# power2.net
KiCad netlist of a schematic drawn in Altium Designer
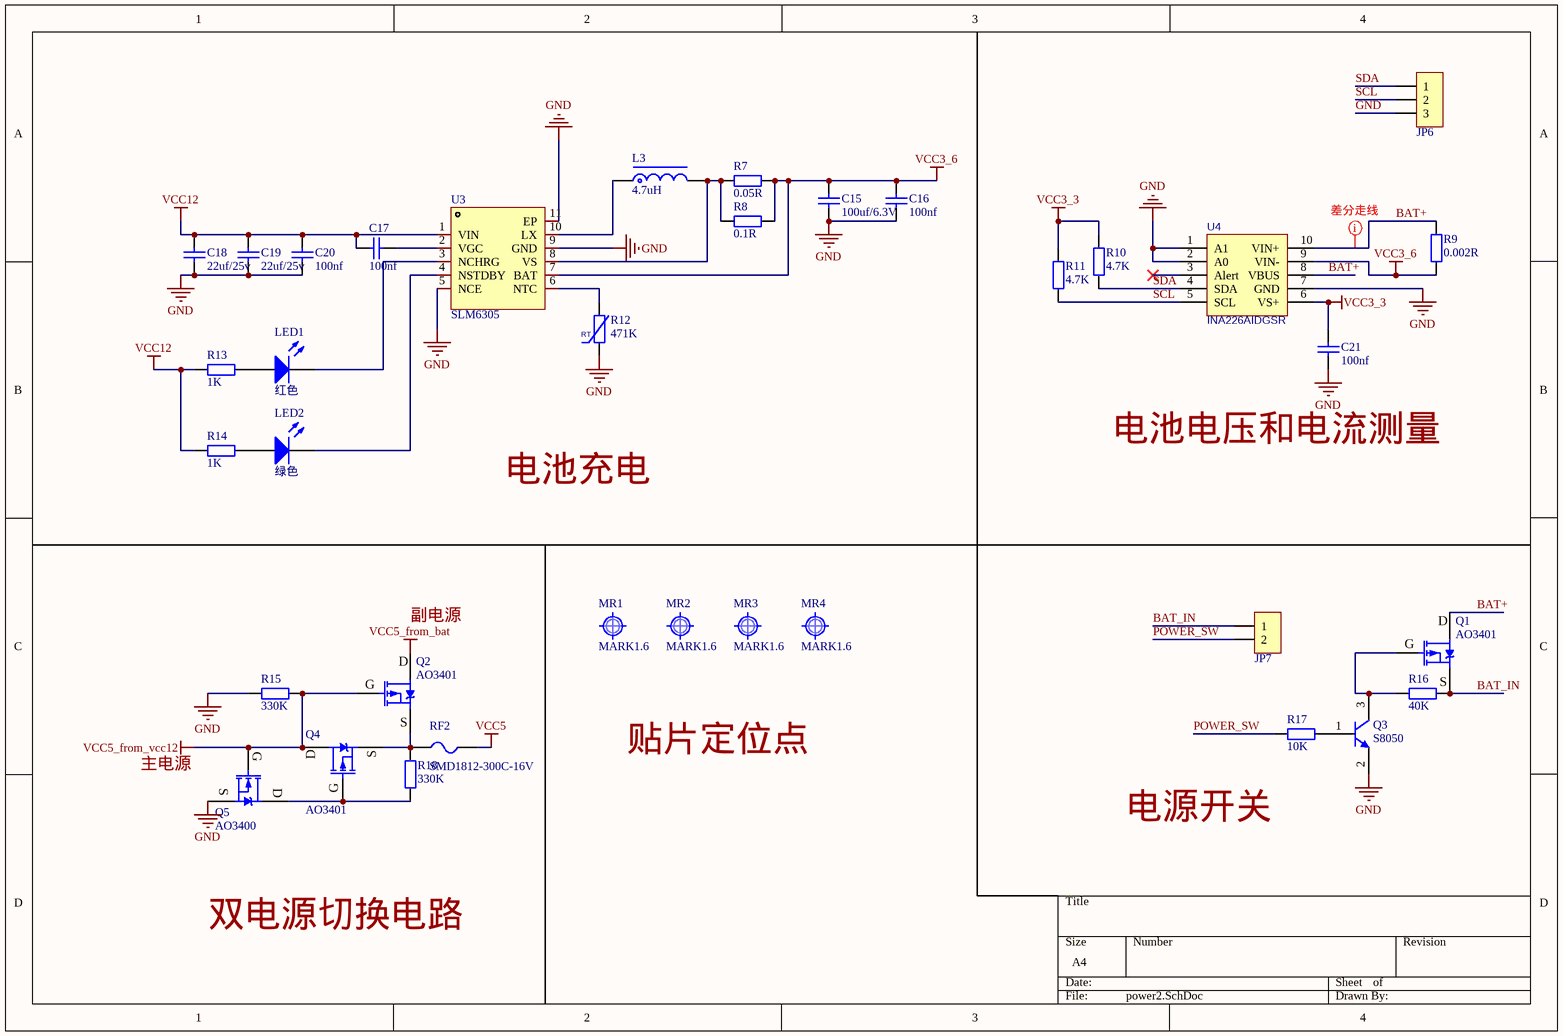
[diagram p0: power2.SchDoc]

(export (version "E")
  (design (tool "Eeschema 10.0.6"))
  (components
    (comp (ref "C15")
      (value "100uf/6.3V")
      (footprint "C1206_L")
      (description "贴片电容/MLCC电容")
      (libsource (lib "0.1 - 电阻-电容-电感-保险丝-晶振-晶体-磁珠-电位器-法拉电容-馈通电容") (part "C"))
    )
    (comp (ref "C16")
      (value "100nf")
      (footprint "C0603_L")
      (description "贴片电容/MLCC电容")
      (libsource (lib "0.1 - 电阻-电容-电感-保险丝-晶振-晶体-磁珠-电位器-法拉电容-馈通电容") (part "C"))
    )
    (comp (ref "C17")
      (value "100nf")
      (footprint "C0603_L")
      (description "贴片电容/MLCC电容")
      (libsource (lib "0.1 - 电阻-电容-电感-保险丝-晶振-晶体-磁珠-电位器-法拉电容-馈通电容") (part "C"))
    )
    (comp (ref "C18")
      (value "22uf/25v")
      (footprint "C0805_L")
      (description "贴片电容/MLCC电容")
      (libsource (lib "0.1 - 电阻-电容-电感-保险丝-晶振-晶体-磁珠-电位器-法拉电容-馈通电容") (part "C"))
    )
    (comp (ref "C19")
      (value "22uf/25v")
      (footprint "C0805_L")
      (description "贴片电容/MLCC电容")
      (libsource (lib "0.1 - 电阻-电容-电感-保险丝-晶振-晶体-磁珠-电位器-法拉电容-馈通电容") (part "C"))
    )
    (comp (ref "C20")
      (value "100nf")
      (footprint "C0603_L")
      (description "贴片电容/MLCC电容")
      (libsource (lib "0.1 - 电阻-电容-电感-保险丝-晶振-晶体-磁珠-电位器-法拉电容-馈通电容") (part "C"))
    )
    (comp (ref "C21")
      (value "100nf")
      (footprint "C0603_L")
      (description "贴片电容/MLCC电容")
      (libsource (lib "0.1 - 电阻-电容-电感-保险丝-晶振-晶体-磁珠-电位器-法拉电容-馈通电容") (part "C"))
    )
    (comp (ref "JP6")
      (value "HDR-1X3")
      (footprint "HDR2.54-LI-3P")
      (description "3P接插件")
      (libsource (lib "5.5 - 2.54mm连接器(KF2EDGK_XH2.54_2.54排针排母)") (part "Header 3"))
    )
    (comp (ref "JP7")
      (value "HDR-1X2")
      (footprint "PH2.0-W-2P")
      (description "2P接插件")
      (libsource (lib "5.4 - 2.0mm连接器(PHB2.0_PHD2.0_2.0排针排母)") (part "Header 2"))
    )
    (comp (ref "L3")
      (value "4.7uH")
      (footprint "CD53")
      (description "CD系列贴片线绕功率电感")
      (libsource (lib "0.1 - 电阻-电容-电感-保险丝-晶振-晶体-磁珠-电位器-法拉电容-馈通电容") (part "L-SMD"))
    )
    (comp (ref "LED1")
      (value "红色")
      (footprint "LED0603_Y")
      (description "贴片LED")
      (libsource (lib "0.3 - LED发光二极管-IR二极管_接收管-光耦") (part "LED"))
    )
    (comp (ref "LED2")
      (value "绿色")
      (footprint "LED0603_Y")
      (description "贴片LED")
      (libsource (lib "0.3 - LED发光二极管-IR二极管_接收管-光耦") (part "LED"))
    )
    (comp (ref "MR1")
      (value "MARK1.6")
      (footprint "Mark 1")
      (description "光学定位点")
      (libsource (lib "0.5 - 按键_开关_蜂鸣器_电池_测试点_Mark点_铜柱") (part "MARK"))
    )
    (comp (ref "MR2")
      (value "MARK1.6")
      (footprint "Mark 1")
      (description "光学定位点")
      (libsource (lib "0.5 - 按键_开关_蜂鸣器_电池_测试点_Mark点_铜柱") (part "MARK"))
    )
    (comp (ref "MR3")
      (value "MARK1.6")
      (footprint "Mark 1")
      (description "光学定位点")
      (libsource (lib "0.5 - 按键_开关_蜂鸣器_电池_测试点_Mark点_铜柱") (part "MARK"))
    )
    (comp (ref "MR4")
      (value "MARK1.6")
      (footprint "Mark 1")
      (description "光学定位点")
      (libsource (lib "0.5 - 按键_开关_蜂鸣器_电池_测试点_Mark点_铜柱") (part "MARK"))
    )
    (comp (ref "Q1")
      (value "AO3401")
      (footprint "SOT23-3N")
      (description "P沟道 30V/4.2A")
      (libsource (lib "0.4 - 三极管-场效应管-可控硅") (part "AO3401"))
    )
    (comp (ref "Q2")
      (value "AO3401")
      (footprint "SOT23-3N")
      (description "P沟道 30V/4.2A")
      (libsource (lib "0.4 - 三极管-场效应管-可控硅") (part "AO3401"))
    )
    (comp (ref "Q3")
      (value "S8050")
      (footprint "SOT23-3M")
      (description "NPN三极管")
      (libsource (lib "0.4 - 三极管-场效应管-可控硅") (part "BCP68"))
    )
    (comp (ref "Q4")
      (value "AO3401")
      (footprint "SOT23-3N")
      (description "P沟道 30V/4.2A")
      (libsource (lib "0.4 - 三极管-场效应管-可控硅") (part "AO3401"))
    )
    (comp (ref "Q5")
      (value "AO3400")
      (footprint "SOT23-3N")
      (description "N沟道 30V/4.2A")
      (libsource (lib "0.4 - 三极管-场效应管-可控硅") (part "AO3400"))
    )
    (comp (ref "R7")
      (value "0.05R")
      (footprint "R1206_L")
      (description "贴片电阻")
      (libsource (lib "0.1 - 电阻-电容-电感-保险丝-晶振-晶体-磁珠-电位器-法拉电容-馈通电容") (part "R"))
    )
    (comp (ref "R8")
      (value "0.1R")
      (footprint "R1206_L")
      (description "贴片电阻")
      (libsource (lib "0.1 - 电阻-电容-电感-保险丝-晶振-晶体-磁珠-电位器-法拉电容-馈通电容") (part "R"))
    )
    (comp (ref "R9")
      (value "0.002R")
      (footprint "R2512_M")
      (description "贴片电阻")
      (libsource (lib "0.1 - 电阻-电容-电感-保险丝-晶振-晶体-磁珠-电位器-法拉电容-馈通电容") (part "R"))
    )
    (comp (ref "R10")
      (value "4.7K")
      (footprint "R0603_L")
      (description "贴片电阻")
      (libsource (lib "0.1 - 电阻-电容-电感-保险丝-晶振-晶体-磁珠-电位器-法拉电容-馈通电容") (part "R"))
    )
    (comp (ref "R11")
      (value "4.7K")
      (footprint "R0603_L")
      (description "贴片电阻")
      (libsource (lib "0.1 - 电阻-电容-电感-保险丝-晶振-晶体-磁珠-电位器-法拉电容-馈通电容") (part "R"))
    )
    (comp (ref "R12")
      (value "471K")
      (footprint "PK0406")
      (description "热敏电阻")
      (libsource (lib "0.1 - 电阻-电容-电感-保险丝-晶振-晶体-磁珠-电位器-法拉电容-馈通电容") (part "RT"))
    )
    (comp (ref "R13")
      (value "1K")
      (footprint "R0603_L")
      (description "贴片电阻")
      (libsource (lib "0.1 - 电阻-电容-电感-保险丝-晶振-晶体-磁珠-电位器-法拉电容-馈通电容") (part "R"))
    )
    (comp (ref "R14")
      (value "1K")
      (footprint "R0603_L")
      (description "贴片电阻")
      (libsource (lib "0.1 - 电阻-电容-电感-保险丝-晶振-晶体-磁珠-电位器-法拉电容-馈通电容") (part "R"))
    )
    (comp (ref "R15")
      (value "330K")
      (footprint "R0603_L")
      (description "贴片电阻")
      (libsource (lib "0.1 - 电阻-电容-电感-保险丝-晶振-晶体-磁珠-电位器-法拉电容-馈通电容") (part "R"))
    )
    (comp (ref "R16")
      (value "40K")
      (footprint "R0603_L")
      (description "贴片电阻")
      (libsource (lib "0.1 - 电阻-电容-电感-保险丝-晶振-晶体-磁珠-电位器-法拉电容-馈通电容") (part "R"))
    )
    (comp (ref "R17")
      (value "10K")
      (footprint "R0603_L")
      (description "贴片电阻")
      (libsource (lib "0.1 - 电阻-电容-电感-保险丝-晶振-晶体-磁珠-电位器-法拉电容-馈通电容") (part "R"))
    )
    (comp (ref "R18")
      (value "330K")
      (footprint "R0603_L")
      (description "贴片电阻")
      (libsource (lib "0.1 - 电阻-电容-电感-保险丝-晶振-晶体-磁珠-电位器-法拉电容-馈通电容") (part "R"))
    )
    (comp (ref "RF2")
      (value "SMD1812-300C-16V")
      (footprint "F1812")
      (description "PPTC自恢复保险丝")
      (libsource (lib "0.1 - 电阻-电容-电感-保险丝-晶振-晶体-磁珠-电位器-法拉电容-馈通电容") (part "FUSE-PPTC"))
    )
    (comp (ref "U3")
      (value "SLM6305")
      (footprint "DFN10-L3.0-W3.0-P0.5_EP")
      (description "1锂电池充电ic 2.5a 4.2v 4V~26V输入")
      (fields (field (name "MANUFACTURER") "无锡松朗微"))
      (libsource (lib "HT") (part "SLM6305"))
    )
    (comp (ref "U4")
      (value "INA226AIDGSR")
      (footprint "MSOP10_N")
      (description "双向电流/功率监视器芯片")
      (libsource (lib "0.8 - 常见芯片") (part "INA226"))
    )
  )
  (nets
    (net (code "1") (name "/BAT+") (class "Default")
      (node (ref "Q1") (pin "3") (pinfunction "D_3") (pintype "passive"))
      (node (ref "R9") (pin "1") (pinfunction "1_1") (pintype "passive"))
      (node (ref "U4") (pin "10") (pinfunction "VIN+_10") (pintype "passive"))
      (node (ref "U4") (pin "8") (pinfunction "VBUS_8") (pintype "passive"))
    )
    (net (code "2") (name "/BAT_IN") (class "Default")
      (node (ref "JP7") (pin "1") (pinfunction "1_1") (pintype "passive"))
      (node (ref "Q1") (pin "2") (pinfunction "S_2") (pintype "passive"))
      (node (ref "R16") (pin "2") (pinfunction "2_2") (pintype "passive"))
    )
    (net (code "3") (name "/POWER_SW") (class "Default")
      (node (ref "JP7") (pin "2") (pinfunction "2_2") (pintype "passive"))
      (node (ref "R17") (pin "1") (pinfunction "1_1") (pintype "passive"))
    )
    (net (code "4") (name "/SCL") (class "Default")
      (node (ref "JP6") (pin "2") (pinfunction "2_2") (pintype "passive"))
      (node (ref "R11") (pin "1") (pinfunction "1_1") (pintype "passive"))
      (node (ref "U4") (pin "5") (pinfunction "SCL_5") (pintype "passive"))
    )
    (net (code "5") (name "/SDA") (class "Default")
      (node (ref "JP6") (pin "1") (pinfunction "1_1") (pintype "passive"))
      (node (ref "R10") (pin "1") (pinfunction "1_1") (pintype "passive"))
      (node (ref "U4") (pin "4") (pinfunction "SDA_4") (pintype "passive"))
    )
    (net (code "6") (name "GND") (class "Default")
      (node (ref "C15") (pin "1") (pinfunction "1_1") (pintype "passive"))
      (node (ref "C16") (pin "1") (pinfunction "1_1") (pintype "passive"))
      (node (ref "C18") (pin "1") (pinfunction "1_1") (pintype "passive"))
      (node (ref "C19") (pin "1") (pinfunction "1_1") (pintype "passive"))
      (node (ref "C20") (pin "2") (pinfunction "2_2") (pintype "passive"))
      (node (ref "C21") (pin "1") (pinfunction "1_1") (pintype "passive"))
      (node (ref "JP6") (pin "3") (pinfunction "3_3") (pintype "passive"))
      (node (ref "Q3") (pin "2") (pinfunction "E_2") (pintype "passive"))
      (node (ref "Q5") (pin "2") (pinfunction "S_2") (pintype "passive"))
      (node (ref "R12") (pin "1") (pinfunction "1_1") (pintype "passive"))
      (node (ref "R15") (pin "2") (pinfunction "2_2") (pintype "passive"))
      (node (ref "U3") (pin "11") (pinfunction "EP_11") (pintype "passive"))
      (node (ref "U3") (pin "5") (pinfunction "NCE_5") (pintype "passive"))
      (node (ref "U3") (pin "9") (pinfunction "GND_9") (pintype "passive"))
      (node (ref "U4") (pin "1") (pinfunction "A1_1") (pintype "passive"))
      (node (ref "U4") (pin "2") (pinfunction "A0_2") (pintype "passive"))
      (node (ref "U4") (pin "7") (pinfunction "GND_7") (pintype "passive"))
    )
    (net (code "7") (name "Net-(LED1-A)") (class "Default")
      (node (ref "LED1") (pin "1") (pinfunction "A_1") (pintype "passive"))
      (node (ref "R13") (pin "2") (pinfunction "2_2") (pintype "passive"))
    )
    (net (code "8") (name "Net-(LED1-K)") (class "Default")
      (node (ref "LED1") (pin "2") (pinfunction "K_2") (pintype "passive"))
      (node (ref "U3") (pin "3") (pinfunction "NCHRG_3") (pintype "passive"))
    )
    (net (code "9") (name "Net-(LED2-A)") (class "Default")
      (node (ref "LED2") (pin "1") (pinfunction "A_1") (pintype "passive"))
      (node (ref "R14") (pin "2") (pinfunction "2_2") (pintype "passive"))
    )
    (net (code "10") (name "Net-(LED2-K)") (class "Default")
      (node (ref "LED2") (pin "2") (pinfunction "K_2") (pintype "passive"))
      (node (ref "U3") (pin "4") (pinfunction "NSTDBY_4") (pintype "passive"))
    )
    (net (code "11") (name "Net-(Q1-G)") (class "Default")
      (node (ref "Q1") (pin "1") (pinfunction "G_1") (pintype "passive"))
      (node (ref "Q3") (pin "3") (pinfunction "C_3") (pintype "passive"))
      (node (ref "R16") (pin "1") (pinfunction "1_1") (pintype "passive"))
    )
    (net (code "12") (name "Net-(Q2-S)") (class "Default")
      (node (ref "Q2") (pin "2") (pinfunction "S_2") (pintype "passive"))
      (node (ref "Q4") (pin "2") (pinfunction "S_2") (pintype "passive"))
      (node (ref "R18") (pin "2") (pinfunction "2_2") (pintype "passive"))
      (node (ref "RF2") (pin "2") (pinfunction "2_2") (pintype "passive"))
    )
    (net (code "13") (name "Net-(Q3-B)") (class "Default")
      (node (ref "Q3") (pin "1") (pinfunction "B_1") (pintype "passive"))
      (node (ref "R17") (pin "2") (pinfunction "2_2") (pintype "passive"))
    )
    (net (code "14") (name "Net-(Q4-G)") (class "Default")
      (node (ref "Q4") (pin "1") (pinfunction "G_1") (pintype "passive"))
      (node (ref "Q5") (pin "3") (pinfunction "D_3") (pintype "passive"))
      (node (ref "R18") (pin "1") (pinfunction "1_1") (pintype "passive"))
    )
    (net (code "15") (name "Net-(U3-LX)") (class "Default")
      (node (ref "L3") (pin "1") (pinfunction "1_1") (pintype "passive"))
      (node (ref "U3") (pin "10") (pinfunction "LX_10") (pintype "passive"))
    )
    (net (code "16") (name "Net-(U3-NTC)") (class "Default")
      (node (ref "R12") (pin "2") (pinfunction "2_2") (pintype "passive"))
      (node (ref "U3") (pin "6") (pinfunction "NTC_6") (pintype "passive"))
    )
    (net (code "17") (name "Net-(U3-VGC)") (class "Default")
      (node (ref "C17") (pin "1") (pinfunction "1_1") (pintype "passive"))
      (node (ref "U3") (pin "2") (pinfunction "VGC_2") (pintype "passive"))
    )
    (net (code "18") (name "Net-(U3-VS)") (class "Default")
      (node (ref "L3") (pin "2") (pinfunction "2_2") (pintype "passive"))
      (node (ref "R7") (pin "1") (pinfunction "1_1") (pintype "passive"))
      (node (ref "R8") (pin "1") (pinfunction "1_1") (pintype "passive"))
      (node (ref "U3") (pin "8") (pinfunction "VS_8") (pintype "passive"))
    )
    (net (code "19") (name "VCC3_3") (class "Default")
      (node (ref "C21") (pin "2") (pinfunction "2_2") (pintype "passive"))
      (node (ref "R10") (pin "2") (pinfunction "2_2") (pintype "passive"))
      (node (ref "R11") (pin "2") (pinfunction "2_2") (pintype "passive"))
      (node (ref "U4") (pin "6") (pinfunction "VS+_6") (pintype "passive"))
    )
    (net (code "20") (name "VCC3_6") (class "Default")
      (node (ref "C15") (pin "2") (pinfunction "2_2") (pintype "passive"))
      (node (ref "C16") (pin "2") (pinfunction "2_2") (pintype "passive"))
      (node (ref "R7") (pin "2") (pinfunction "2_2") (pintype "passive"))
      (node (ref "R8") (pin "2") (pinfunction "2_2") (pintype "passive"))
      (node (ref "R9") (pin "2") (pinfunction "2_2") (pintype "passive"))
      (node (ref "U3") (pin "7") (pinfunction "BAT_7") (pintype "passive"))
      (node (ref "U4") (pin "9") (pinfunction "VIN-_9") (pintype "passive"))
    )
    (net (code "21") (name "VCC5") (class "Default")
      (node (ref "RF2") (pin "1") (pinfunction "1_1") (pintype "passive"))
    )
    (net (code "22") (name "VCC5_from_bat") (class "Default")
      (node (ref "Q2") (pin "3") (pinfunction "D_3") (pintype "passive"))
    )
    (net (code "23") (name "VCC5_from_vcc12") (class "Default")
      (node (ref "Q2") (pin "1") (pinfunction "G_1") (pintype "passive"))
      (node (ref "Q4") (pin "3") (pinfunction "D_3") (pintype "passive"))
      (node (ref "Q5") (pin "1") (pinfunction "G_1") (pintype "passive"))
      (node (ref "R15") (pin "1") (pinfunction "1_1") (pintype "passive"))
    )
    (net (code "24") (name "VCC12") (class "Default")
      (node (ref "C17") (pin "2") (pinfunction "2_2") (pintype "passive"))
      (node (ref "C18") (pin "2") (pinfunction "2_2") (pintype "passive"))
      (node (ref "C19") (pin "2") (pinfunction "2_2") (pintype "passive"))
      (node (ref "C20") (pin "1") (pinfunction "1_1") (pintype "passive"))
      (node (ref "R13") (pin "1") (pinfunction "1_1") (pintype "passive"))
      (node (ref "R14") (pin "1") (pinfunction "1_1") (pintype "passive"))
      (node (ref "U3") (pin "1") (pinfunction "VIN_1") (pintype "passive"))
    )
    (net (code "25") (name "unconnected-(U4-Alert-Pad3)") (class "Default")
      (node (ref "U4") (pin "3") (pinfunction "Alert_3") (pintype "passive+no_connect"))
    )
  )
)
